# Guri_AVR.net
KiCad netlist of a schematic drawn in EAGLE
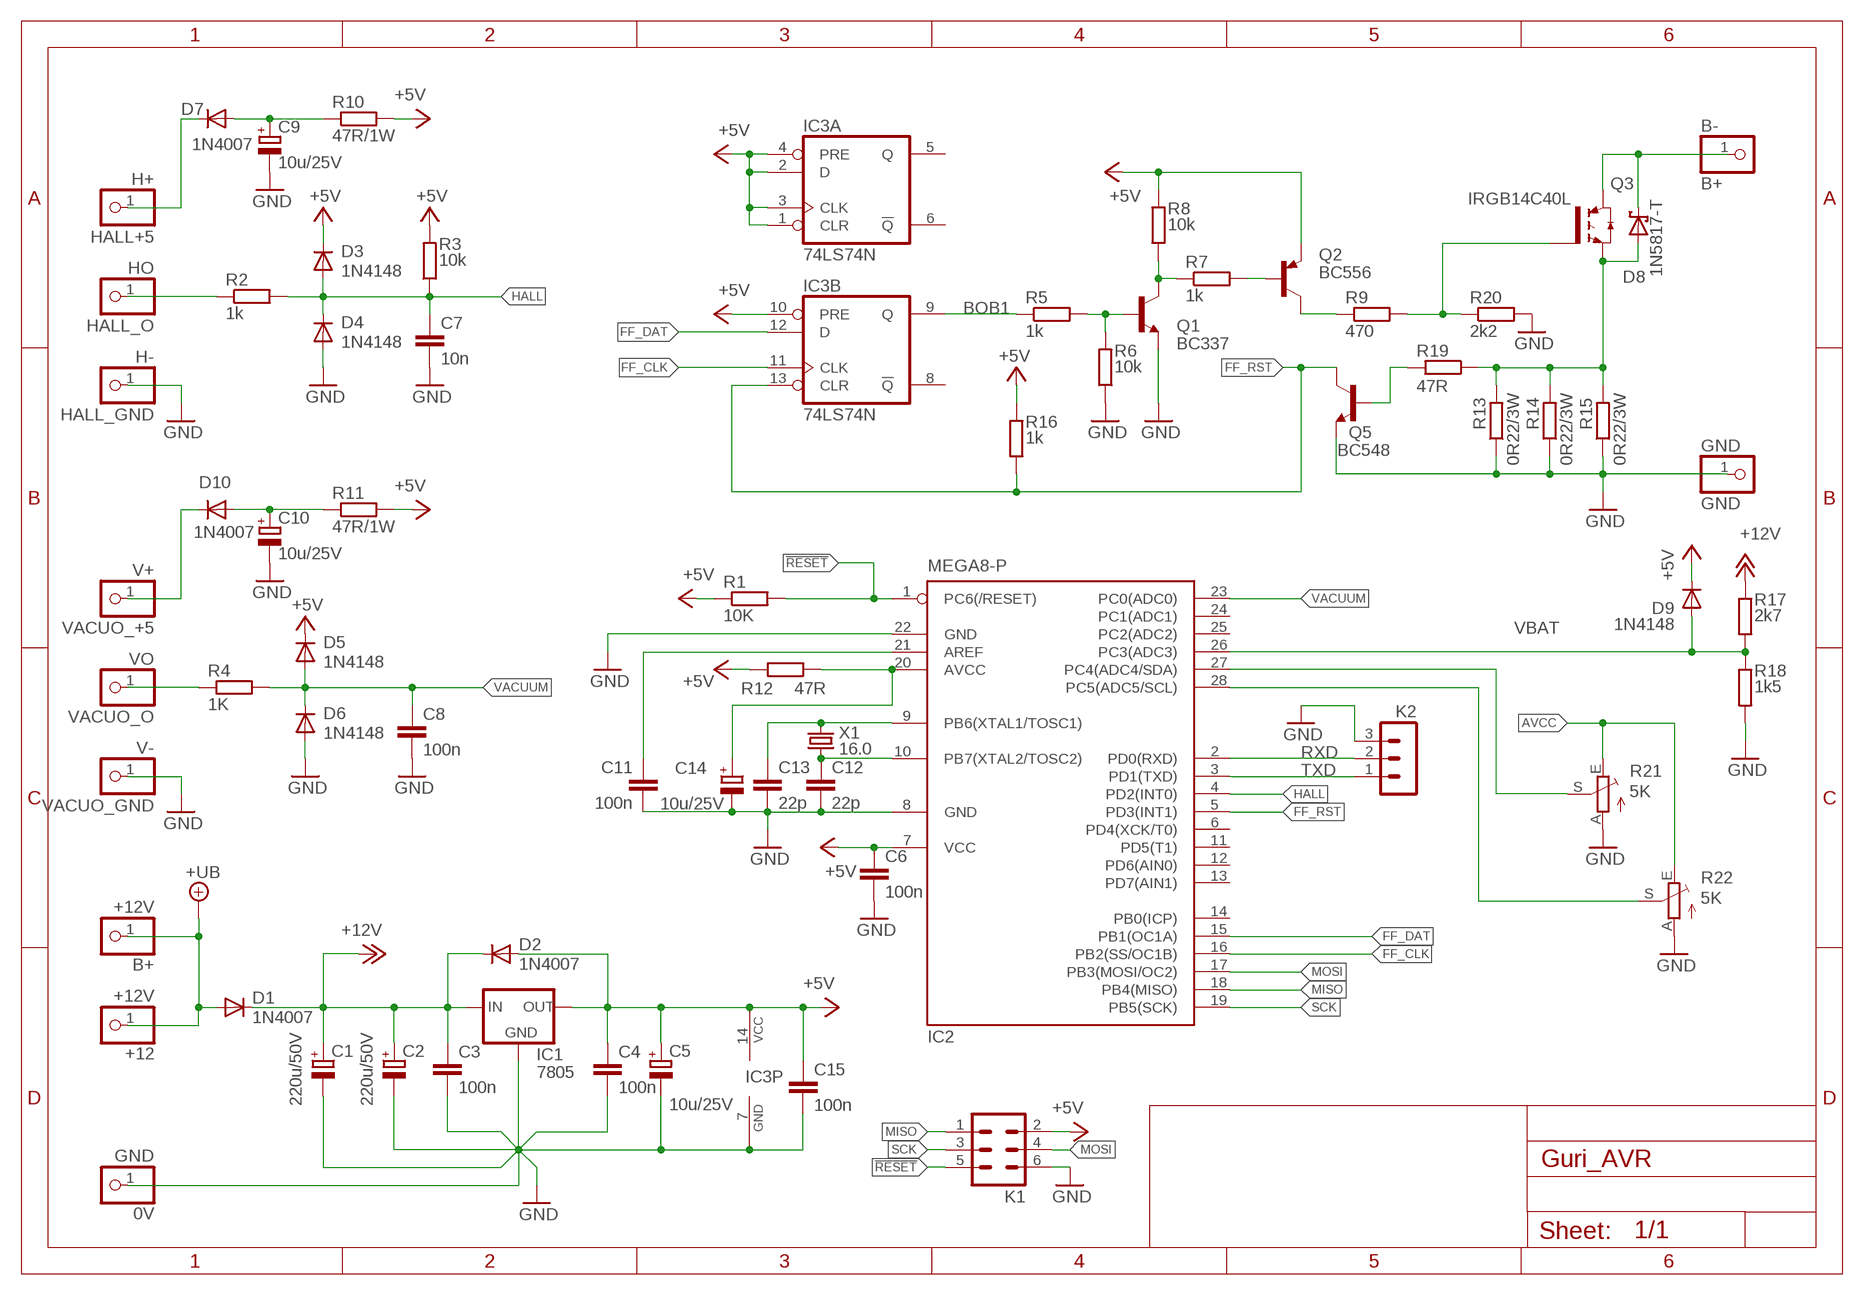
[diagram p0: schematic, sheet 1]

(export (version "E")
  (design (tool "Eeschema 10.0.6"))
  (components
    (comp (ref "+12")
      (value "+12V")
      (footprint "eagle-import:1X01")
      (libsource (lib "eagle-import") (part "PINHD-1X1"))
    )
    (comp (ref "0V")
      (value "GND")
      (footprint "eagle-import:1X01")
      (libsource (lib "eagle-import") (part "PINHD-1X1"))
    )
    (comp (ref "B+")
      (value "+12V")
      (footprint "eagle-import:1X01")
      (libsource (lib "eagle-import") (part "PINHD-1X1"))
    )
    (comp (ref "B-")
      (value "B+")
      (footprint "eagle-import:1X01")
      (libsource (lib "eagle-import") (part "PINHD-1X1"))
    )
    (comp (ref "C1")
      (value "220u/50V")
      (footprint "eagle-import:E5-10,5")
      (libsource (lib "eagle-import") (part "CPOL-EUE5-10.5"))
    )
    (comp (ref "C2")
      (value "220u/50V")
      (footprint "eagle-import:E5-10,5")
      (libsource (lib "eagle-import") (part "CPOL-EUE5-10.5"))
    )
    (comp (ref "C3")
      (value "100n")
      (footprint "eagle-import:C050-025X075")
      (libsource (lib "eagle-import") (part "C-EU050-025X075"))
    )
    (comp (ref "C4")
      (value "100n")
      (footprint "eagle-import:C050-025X075")
      (libsource (lib "eagle-import") (part "C-EU050-025X075"))
    )
    (comp (ref "C5")
      (value "10u/25V")
      (footprint "eagle-import:E2-5")
      (libsource (lib "eagle-import") (part "CPOL-EUE2-5"))
    )
    (comp (ref "C6")
      (value "100n")
      (footprint "eagle-import:C050-025X075")
      (libsource (lib "eagle-import") (part "C-EU050-025X075"))
    )
    (comp (ref "C7")
      (value "10n")
      (footprint "eagle-import:C050-025X075")
      (libsource (lib "eagle-import") (part "C-EU050-025X075"))
    )
    (comp (ref "C8")
      (value "100n")
      (footprint "eagle-import:C050-025X075")
      (libsource (lib "eagle-import") (part "C-EU050-025X075"))
    )
    (comp (ref "C9")
      (value "10u/25V")
      (footprint "eagle-import:E2-5")
      (libsource (lib "eagle-import") (part "CPOL-EUE2-5"))
    )
    (comp (ref "C10")
      (value "10u/25V")
      (footprint "eagle-import:E2-5")
      (libsource (lib "eagle-import") (part "CPOL-EUE2-5"))
    )
    (comp (ref "C11")
      (value "100n")
      (footprint "eagle-import:C050-025X075")
      (libsource (lib "eagle-import") (part "C-EU050-025X075"))
    )
    (comp (ref "C12")
      (value "22p")
      (footprint "eagle-import:C050-024X044")
      (libsource (lib "eagle-import") (part "C-EU050-024X044"))
    )
    (comp (ref "C13")
      (value "22p")
      (footprint "eagle-import:C050-024X044")
      (libsource (lib "eagle-import") (part "C-EU050-024X044"))
    )
    (comp (ref "C14")
      (value "10u/25V")
      (footprint "eagle-import:E2-5")
      (libsource (lib "eagle-import") (part "CPOL-EUE2-5"))
    )
    (comp (ref "C15")
      (value "100n")
      (footprint "eagle-import:C050-025X075")
      (libsource (lib "eagle-import") (part "C-EU050-025X075"))
    )
    (comp (ref "D1")
      (value "1N4007")
      (footprint "eagle-import:D-7.5")
      (libsource (lib "eagle-import") (part "DIODE-D-7.5"))
    )
    (comp (ref "D2")
      (value "1N4007")
      (footprint "eagle-import:D-7.5")
      (libsource (lib "eagle-import") (part "DIODE-D-7.5"))
    )
    (comp (ref "D3")
      (value "1N4148")
      (footprint "eagle-import:DO35-7")
      (libsource (lib "eagle-import") (part "1N4148DO35-7"))
    )
    (comp (ref "D4")
      (value "1N4148")
      (footprint "eagle-import:DO35-7")
      (libsource (lib "eagle-import") (part "1N4148DO35-7"))
    )
    (comp (ref "D5")
      (value "1N4148")
      (footprint "eagle-import:DO35-7")
      (libsource (lib "eagle-import") (part "1N4148DO35-7"))
    )
    (comp (ref "D6")
      (value "1N4148")
      (footprint "eagle-import:DO35-7")
      (libsource (lib "eagle-import") (part "1N4148DO35-7"))
    )
    (comp (ref "D7")
      (value "1N4007")
      (footprint "eagle-import:D-7.5")
      (libsource (lib "eagle-import") (part "DIODE-D-7.5"))
    )
    (comp (ref "D8")
      (value "1N5817-T")
      (footprint "eagle-import:DO41-7.6")
      (libsource (lib "eagle-import") (part "1N5817-T"))
    )
    (comp (ref "D9")
      (value "1N4148")
      (footprint "eagle-import:DO35-7")
      (libsource (lib "eagle-import") (part "1N4148DO35-7"))
    )
    (comp (ref "D10")
      (value "1N4007")
      (footprint "eagle-import:D-7.5")
      (libsource (lib "eagle-import") (part "DIODE-D-7.5"))
    )
    (comp (ref "GND")
      (value "GND")
      (footprint "eagle-import:1X01")
      (libsource (lib "eagle-import") (part "PINHD-1X1"))
    )
    (comp (ref "H+")
      (value "HALL+5")
      (footprint "eagle-import:1X01")
      (libsource (lib "eagle-import") (part "PINHD-1X1"))
    )
    (comp (ref "H-")
      (value "HALL_GND")
      (footprint "eagle-import:1X01")
      (libsource (lib "eagle-import") (part "PINHD-1X1"))
    )
    (comp (ref "HO")
      (value "HALL_O")
      (footprint "eagle-import:1X01")
      (libsource (lib "eagle-import") (part "PINHD-1X1"))
    )
    (comp (ref "IC1")
      (value "7805")
      (footprint "eagle-import:78XXS")
      (libsource (lib "eagle-import") (part "78XXS"))
    )
    (comp (ref "IC2")
      (value "MEGA8-P")
      (footprint "eagle-import:DIL28-3")
      (libsource (lib "eagle-import") (part "MEGA8-P"))
    )
    (comp (ref "IC3")
      (value "74LS74N")
      (footprint "eagle-import:DIL14")
      (libsource (lib "eagle-import") (part "7474NLS"))
    )
    (comp (ref "K1")
      (value "ML6")
      (footprint "eagle-import:ML6")
      (libsource (lib "eagle-import") (part "ML6"))
    )
    (comp (ref "K2")
      (value "MA03-1")
      (footprint "eagle-import:MA03-1")
      (libsource (lib "eagle-import") (part "MA03-1"))
    )
    (comp (ref "Q1")
      (value "BC337")
      (footprint "eagle-import:TO92-EBC")
      (libsource (lib "eagle-import") (part "BC338"))
    )
    (comp (ref "Q2")
      (value "BC556")
      (footprint "eagle-import:TO92-EBC")
      (libsource (lib "eagle-import") (part "BC556"))
    )
    (comp (ref "Q3")
      (value "IRGB14C40L")
      (footprint "eagle-import:TO262-V")
      (libsource (lib "eagle-import") (part "IRG4BC15UD--L"))
    )
    (comp (ref "Q5")
      (value "BC548")
      (footprint "eagle-import:TO92-EBC")
      (libsource (lib "eagle-import") (part "BC338"))
    )
    (comp (ref "R1")
      (value "10K")
      (footprint "eagle-import:0207_7L")
      (libsource (lib "eagle-import") (part "R-EU_0207/7L"))
    )
    (comp (ref "R2")
      (value "1k")
      (footprint "eagle-import:0207_7L")
      (libsource (lib "eagle-import") (part "R-EU_0207/7L"))
    )
    (comp (ref "R3")
      (value "10k")
      (footprint "eagle-import:0207_7L")
      (libsource (lib "eagle-import") (part "R-EU_0207/7L"))
    )
    (comp (ref "R4")
      (value "1K")
      (footprint "eagle-import:0207_7L")
      (libsource (lib "eagle-import") (part "R-EU_0207/7L"))
    )
    (comp (ref "R5")
      (value "1k")
      (footprint "eagle-import:0207_7L")
      (libsource (lib "eagle-import") (part "R-EU_0207/7L"))
    )
    (comp (ref "R6")
      (value "10k")
      (footprint "eagle-import:0207_7L")
      (libsource (lib "eagle-import") (part "R-EU_0207/7L"))
    )
    (comp (ref "R7")
      (value "1k")
      (footprint "eagle-import:0207_7L")
      (libsource (lib "eagle-import") (part "R-EU_0207/7L"))
    )
    (comp (ref "R8")
      (value "10k")
      (footprint "eagle-import:0207_7L")
      (libsource (lib "eagle-import") (part "R-EU_0207/7L"))
    )
    (comp (ref "R9")
      (value "470")
      (footprint "eagle-import:0207_7L")
      (libsource (lib "eagle-import") (part "R-EU_0207/7L"))
    )
    (comp (ref "R10")
      (value "47R/1W")
      (footprint "eagle-import:0207_7L")
      (libsource (lib "eagle-import") (part "R-EU_0207/7L"))
    )
    (comp (ref "R11")
      (value "47R/1W")
      (footprint "eagle-import:0207_7L")
      (libsource (lib "eagle-import") (part "R-EU_0207/7L"))
    )
    (comp (ref "R12")
      (value "47R")
      (footprint "eagle-import:0207_7L")
      (libsource (lib "eagle-import") (part "R-EU_0207/7L"))
    )
    (comp (ref "R13")
      (value "0R22/3W")
      (footprint "eagle-import:0309_10")
      (libsource (lib "eagle-import") (part "R-EU_0309/10"))
    )
    (comp (ref "R14")
      (value "0R22/3W")
      (footprint "eagle-import:0309_10")
      (libsource (lib "eagle-import") (part "R-EU_0309/10"))
    )
    (comp (ref "R15")
      (value "0R22/3W")
      (footprint "eagle-import:0309_10")
      (libsource (lib "eagle-import") (part "R-EU_0309/10"))
    )
    (comp (ref "R16")
      (value "1k")
      (footprint "eagle-import:0207_7L")
      (libsource (lib "eagle-import") (part "R-EU_0207/7L"))
    )
    (comp (ref "R17")
      (value "2k7")
      (footprint "eagle-import:0207_7L")
      (libsource (lib "eagle-import") (part "R-EU_0207/7L"))
    )
    (comp (ref "R18")
      (value "1k5")
      (footprint "eagle-import:0207_7L")
      (libsource (lib "eagle-import") (part "R-EU_0207/7L"))
    )
    (comp (ref "R19")
      (value "47R")
      (footprint "eagle-import:0207_7L")
      (libsource (lib "eagle-import") (part "R-EU_0207/7L"))
    )
    (comp (ref "R20")
      (value "2k2")
      (footprint "eagle-import:0207_7L")
      (libsource (lib "eagle-import") (part "R-EU_0207/7L"))
    )
    (comp (ref "R21")
      (value "5K")
      (footprint "eagle-import:ECP10P")
      (libsource (lib "eagle-import") (part "TRIM_EU-ECP10P"))
    )
    (comp (ref "R22")
      (value "5K")
      (footprint "eagle-import:ECP10P")
      (libsource (lib "eagle-import") (part "TRIM_EU-ECP10P"))
    )
    (comp (ref "V+")
      (value "VACUO_+5")
      (footprint "eagle-import:1X01")
      (libsource (lib "eagle-import") (part "PINHD-1X1"))
    )
    (comp (ref "V-")
      (value "VACUO_GND")
      (footprint "eagle-import:1X01")
      (libsource (lib "eagle-import") (part "PINHD-1X1"))
    )
    (comp (ref "VO")
      (value "VACUO_O")
      (footprint "eagle-import:1X01")
      (libsource (lib "eagle-import") (part "PINHD-1X1"))
    )
    (comp (ref "X1")
      (value "16.0")
      (footprint "eagle-import:HC49_S")
      (libsource (lib "eagle-import") (part "CRYSTALHC49S"))
    )
  )
  (nets
    (net (code "1") (name "+5V") (class "Default")
      (node (ref "C15") (pin "1") (pinfunction "1_1") (pintype "passive"))
      (node (ref "C4") (pin "1") (pinfunction "1_1") (pintype "passive"))
      (node (ref "C5") (pin "+") (pinfunction "+_+") (pintype "passive"))
      (node (ref "C6") (pin "1") (pinfunction "1_1") (pintype "passive"))
      (node (ref "D2") (pin "A") (pinfunction "A_A") (pintype "passive"))
      (node (ref "D3") (pin "C") (pinfunction "C_C") (pintype "passive"))
      (node (ref "D5") (pin "C") (pinfunction "C_C") (pintype "passive"))
      (node (ref "D9") (pin "C") (pinfunction "C_C") (pintype "passive"))
      (node (ref "IC1") (pin "OUT") (pinfunction "OUT_OUT") (pintype "passive"))
      (node (ref "IC2") (pin "7") (pinfunction "VCC_7") (pintype "power_in"))
      (node (ref "IC3") (pin "1") (pinfunction "CLR_1") (pintype "input"))
      (node (ref "IC3") (pin "10") (pinfunction "PRE_10") (pintype "input"))
      (node (ref "IC3") (pin "14") (pinfunction "VCC_14") (pintype "power_in"))
      (node (ref "IC3") (pin "2") (pinfunction "D_2") (pintype "input"))
      (node (ref "IC3") (pin "3") (pinfunction "CLK_3") (pintype "input"))
      (node (ref "IC3") (pin "4") (pinfunction "PRE_4") (pintype "input"))
      (node (ref "K1") (pin "2") (pinfunction "2_2") (pintype "passive"))
      (node (ref "Q2") (pin "E") (pinfunction "E_E") (pintype "passive"))
      (node (ref "R1") (pin "3") (pinfunction "1_3") (pintype "passive"))
      (node (ref "R10") (pin "4") (pinfunction "2_4") (pintype "passive"))
      (node (ref "R11") (pin "4") (pinfunction "2_4") (pintype "passive"))
      (node (ref "R12") (pin "4") (pinfunction "2_4") (pintype "passive"))
      (node (ref "R16") (pin "4") (pinfunction "2_4") (pintype "passive"))
      (node (ref "R3") (pin "4") (pinfunction "2_4") (pintype "passive"))
      (node (ref "R8") (pin "4") (pinfunction "2_4") (pintype "passive"))
    )
    (net (code "2") (name "+12V") (class "Default")
      (node (ref "C1") (pin "+") (pinfunction "+_+") (pintype "passive"))
      (node (ref "C2") (pin "+") (pinfunction "+_+") (pintype "passive"))
      (node (ref "C3") (pin "1") (pinfunction "1_1") (pintype "passive"))
      (node (ref "D1") (pin "C") (pinfunction "C_C") (pintype "passive"))
      (node (ref "D2") (pin "C") (pinfunction "C_C") (pintype "passive"))
      (node (ref "IC1") (pin "IN") (pinfunction "IN_IN") (pintype "input"))
      (node (ref "R17") (pin "3") (pinfunction "1_3") (pintype "passive"))
    )
    (net (code "3") (name "+UB") (class "Default")
      (node (ref "+12") (pin "1") (pinfunction "1_1") (pintype "passive"))
      (node (ref "B+") (pin "1") (pinfunction "1_1") (pintype "passive"))
      (node (ref "D1") (pin "A") (pinfunction "A_A") (pintype "passive"))
    )
    (net (code "4") (name "/BOB1") (class "Default")
      (node (ref "IC3") (pin "9") (pinfunction "Q_9") (pintype "output"))
      (node (ref "R5") (pin "3") (pinfunction "1_3") (pintype "passive"))
    )
    (net (code "5") (name "/RXD") (class "Default")
      (node (ref "IC2") (pin "2") (pinfunction "PD0(RXD)_2") (pintype "bidirectional"))
      (node (ref "K2") (pin "2") (pinfunction "2_2") (pintype "passive"))
    )
    (net (code "6") (name "/TXD") (class "Default")
      (node (ref "IC2") (pin "3") (pinfunction "PD1(TXD)_3") (pintype "bidirectional"))
      (node (ref "K2") (pin "1") (pinfunction "1_1") (pintype "passive"))
    )
    (net (code "7") (name "/VBAT") (class "Default")
      (node (ref "D9") (pin "A") (pinfunction "A_A") (pintype "passive"))
      (node (ref "IC2") (pin "26") (pinfunction "PC3(ADC3)_26") (pintype "bidirectional"))
      (node (ref "R17") (pin "4") (pinfunction "2_4") (pintype "passive"))
      (node (ref "R18") (pin "3") (pinfunction "1_3") (pintype "passive"))
    )
    (net (code "8") (name "/~{RESET}") (class "Default")
      (node (ref "IC2") (pin "1") (pinfunction "PC6(/RESET)_1") (pintype "bidirectional"))
      (node (ref "K1") (pin "5") (pinfunction "5_5") (pintype "passive"))
      (node (ref "R1") (pin "4") (pinfunction "2_4") (pintype "passive"))
    )
    (net (code "9") (name "AVCC") (class "Default")
      (node (ref "C14") (pin "+") (pinfunction "+_+") (pintype "passive"))
      (node (ref "IC2") (pin "20") (pinfunction "AVCC_20") (pintype "power_in"))
      (node (ref "R12") (pin "3") (pinfunction "1_3") (pintype "passive"))
      (node (ref "R21") (pin "E") (pinfunction "E_E") (pintype "passive"))
      (node (ref "R22") (pin "E") (pinfunction "E_E") (pintype "passive"))
    )
    (net (code "10") (name "FF_CLK") (class "Default")
      (node (ref "IC2") (pin "16") (pinfunction "PB2(SS/OC1B)_16") (pintype "bidirectional"))
      (node (ref "IC3") (pin "11") (pinfunction "CLK_11") (pintype "input"))
    )
    (net (code "11") (name "FF_DAT") (class "Default")
      (node (ref "IC2") (pin "15") (pinfunction "PB1(OC1A)_15") (pintype "bidirectional"))
      (node (ref "IC3") (pin "12") (pinfunction "D_12") (pintype "input"))
    )
    (net (code "12") (name "FF_RST") (class "Default")
      (node (ref "IC2") (pin "5") (pinfunction "PD3(INT1)_5") (pintype "bidirectional"))
      (node (ref "IC3") (pin "13") (pinfunction "CLR_13") (pintype "input"))
      (node (ref "Q5") (pin "C") (pinfunction "C_C") (pintype "passive"))
      (node (ref "R16") (pin "3") (pinfunction "1_3") (pintype "passive"))
    )
    (net (code "13") (name "GND") (class "Default")
      (node (ref "0V") (pin "1") (pinfunction "1_1") (pintype "passive"))
      (node (ref "C1") (pin "-") (pinfunction "-_-") (pintype "passive"))
      (node (ref "C10") (pin "-") (pinfunction "-_-") (pintype "passive"))
      (node (ref "C11") (pin "2") (pinfunction "2_2") (pintype "passive"))
      (node (ref "C12") (pin "2") (pinfunction "2_2") (pintype "passive"))
      (node (ref "C13") (pin "2") (pinfunction "2_2") (pintype "passive"))
      (node (ref "C14") (pin "-") (pinfunction "-_-") (pintype "passive"))
      (node (ref "C15") (pin "2") (pinfunction "2_2") (pintype "passive"))
      (node (ref "C2") (pin "-") (pinfunction "-_-") (pintype "passive"))
      (node (ref "C3") (pin "2") (pinfunction "2_2") (pintype "passive"))
      (node (ref "C4") (pin "2") (pinfunction "2_2") (pintype "passive"))
      (node (ref "C5") (pin "-") (pinfunction "-_-") (pintype "passive"))
      (node (ref "C6") (pin "2") (pinfunction "2_2") (pintype "passive"))
      (node (ref "C7") (pin "2") (pinfunction "2_2") (pintype "passive"))
      (node (ref "C8") (pin "2") (pinfunction "2_2") (pintype "passive"))
      (node (ref "C9") (pin "-") (pinfunction "-_-") (pintype "passive"))
      (node (ref "D4") (pin "A") (pinfunction "A_A") (pintype "passive"))
      (node (ref "D6") (pin "A") (pinfunction "A_A") (pintype "passive"))
      (node (ref "GND") (pin "1") (pinfunction "1_1") (pintype "passive"))
      (node (ref "H-") (pin "1") (pinfunction "1_1") (pintype "passive"))
      (node (ref "IC1") (pin "GND") (pinfunction "GND_GND") (pintype "input"))
      (node (ref "IC2") (pin "22") (pinfunction "GND_22") (pintype "power_in"))
      (node (ref "IC2") (pin "8") (pinfunction "GND_8") (pintype "power_in"))
      (node (ref "IC3") (pin "7") (pinfunction "GND_7") (pintype "power_in"))
      (node (ref "K1") (pin "6") (pinfunction "6_6") (pintype "passive"))
      (node (ref "K2") (pin "3") (pinfunction "3_3") (pintype "passive"))
      (node (ref "Q1") (pin "E") (pinfunction "E_E") (pintype "passive"))
      (node (ref "Q5") (pin "E") (pinfunction "E_E") (pintype "passive"))
      (node (ref "R13") (pin "1") (pinfunction "1_1") (pintype "passive"))
      (node (ref "R14") (pin "1") (pinfunction "1_1") (pintype "passive"))
      (node (ref "R15") (pin "1") (pinfunction "1_1") (pintype "passive"))
      (node (ref "R18") (pin "4") (pinfunction "2_4") (pintype "passive"))
      (node (ref "R20") (pin "4") (pinfunction "2_4") (pintype "passive"))
      (node (ref "R21") (pin "A") (pinfunction "A_A") (pintype "passive"))
      (node (ref "R22") (pin "A") (pinfunction "A_A") (pintype "passive"))
      (node (ref "R6") (pin "3") (pinfunction "1_3") (pintype "passive"))
      (node (ref "V-") (pin "1") (pinfunction "1_1") (pintype "passive"))
    )
    (net (code "14") (name "HALL") (class "Default")
      (node (ref "C7") (pin "1") (pinfunction "1_1") (pintype "passive"))
      (node (ref "D3") (pin "A") (pinfunction "A_A") (pintype "passive"))
      (node (ref "D4") (pin "C") (pinfunction "C_C") (pintype "passive"))
      (node (ref "IC2") (pin "4") (pinfunction "PD2(INT0)_4") (pintype "bidirectional"))
      (node (ref "R2") (pin "4") (pinfunction "2_4") (pintype "passive"))
      (node (ref "R3") (pin "3") (pinfunction "1_3") (pintype "passive"))
    )
    (net (code "15") (name "MISO") (class "Default")
      (node (ref "IC2") (pin "18") (pinfunction "PB4(MISO)_18") (pintype "bidirectional"))
      (node (ref "K1") (pin "1") (pinfunction "1_1") (pintype "passive"))
    )
    (net (code "16") (name "MOSI") (class "Default")
      (node (ref "IC2") (pin "17") (pinfunction "PB3(MOSI/OC2)_17") (pintype "bidirectional"))
      (node (ref "K1") (pin "4") (pinfunction "4_4") (pintype "passive"))
    )
    (net (code "17") (name "Net-(D7-PadC)") (class "Default")
      (node (ref "D7") (pin "C") (pinfunction "C_C") (pintype "passive"))
      (node (ref "H+") (pin "1") (pinfunction "1_1") (pintype "passive"))
    )
    (net (code "18") (name "Net-(D10-PadC)") (class "Default")
      (node (ref "D10") (pin "C") (pinfunction "C_C") (pintype "passive"))
      (node (ref "V+") (pin "1") (pinfunction "1_1") (pintype "passive"))
    )
    (net (code "19") (name "Net-(IC2-AREF)") (class "Default")
      (node (ref "C11") (pin "1") (pinfunction "1_1") (pintype "passive"))
      (node (ref "IC2") (pin "21") (pinfunction "AREF_21") (pintype "passive"))
    )
    (net (code "20") (name "Net-(IC2-PB6(XTAL1{slash}TOSC1))") (class "Default")
      (node (ref "C13") (pin "1") (pinfunction "1_1") (pintype "passive"))
      (node (ref "IC2") (pin "9") (pinfunction "PB6(XTAL1/TOSC1)_9") (pintype "bidirectional"))
      (node (ref "X1") (pin "2") (pinfunction "2_2") (pintype "passive"))
    )
    (net (code "21") (name "Net-(IC2-PB7(XTAL2{slash}TOSC2))") (class "Default")
      (node (ref "C12") (pin "1") (pinfunction "1_1") (pintype "passive"))
      (node (ref "IC2") (pin "10") (pinfunction "PB7(XTAL2/TOSC2)_10") (pintype "bidirectional"))
      (node (ref "X1") (pin "1") (pinfunction "1_1") (pintype "passive"))
    )
    (net (code "22") (name "Net-(IC2-PC4(ADC4{slash}SDA))") (class "Default")
      (node (ref "IC2") (pin "27") (pinfunction "PC4(ADC4/SDA)_27") (pintype "bidirectional"))
      (node (ref "R21") (pin "S") (pinfunction "S_S") (pintype "passive"))
    )
    (net (code "23") (name "Net-(IC2-PC5(ADC5{slash}SCL))") (class "Default")
      (node (ref "IC2") (pin "28") (pinfunction "PC5(ADC5/SCL)_28") (pintype "bidirectional"))
      (node (ref "R22") (pin "S") (pinfunction "S_S") (pintype "passive"))
    )
    (net (code "24") (name "Net-(Q3-C)") (class "Default")
      (node (ref "B-") (pin "1") (pinfunction "1_1") (pintype "passive"))
      (node (ref "D8") (pin "C") (pinfunction "C_C") (pintype "passive"))
      (node (ref "Q3") (pin "2") (pinfunction "C_2") (pintype "passive"))
    )
    (net (code "25") (name "Net-(Q3-E)") (class "Default")
      (node (ref "D8") (pin "A") (pinfunction "A_A") (pintype "passive"))
      (node (ref "Q3") (pin "3") (pinfunction "E_3") (pintype "passive"))
      (node (ref "R13") (pin "2") (pinfunction "2_2") (pintype "passive"))
      (node (ref "R14") (pin "2") (pinfunction "2_2") (pintype "passive"))
      (node (ref "R15") (pin "2") (pinfunction "2_2") (pintype "passive"))
      (node (ref "R19") (pin "3") (pinfunction "1_3") (pintype "passive"))
    )
    (net (code "26") (name "Net-(Q3-G)") (class "Default")
      (node (ref "Q3") (pin "1") (pinfunction "G_1") (pintype "passive"))
      (node (ref "R20") (pin "3") (pinfunction "1_3") (pintype "passive"))
      (node (ref "R9") (pin "4") (pinfunction "2_4") (pintype "passive"))
    )
    (net (code "27") (name "Net-(R2-1)") (class "Default")
      (node (ref "HO") (pin "1") (pinfunction "1_1") (pintype "passive"))
      (node (ref "R2") (pin "3") (pinfunction "1_3") (pintype "passive"))
    )
    (net (code "28") (name "Net-(R4-1)") (class "Default")
      (node (ref "R4") (pin "3") (pinfunction "1_3") (pintype "passive"))
      (node (ref "VO") (pin "1") (pinfunction "1_1") (pintype "passive"))
    )
    (net (code "29") (name "Net-(R5-2)") (class "Default")
      (node (ref "Q1") (pin "B") (pinfunction "B_B") (pintype "passive"))
      (node (ref "R5") (pin "4") (pinfunction "2_4") (pintype "passive"))
      (node (ref "R6") (pin "4") (pinfunction "2_4") (pintype "passive"))
    )
    (net (code "30") (name "Net-(R7-1)") (class "Default")
      (node (ref "Q1") (pin "C") (pinfunction "C_C") (pintype "passive"))
      (node (ref "R7") (pin "3") (pinfunction "1_3") (pintype "passive"))
      (node (ref "R8") (pin "3") (pinfunction "1_3") (pintype "passive"))
    )
    (net (code "31") (name "Net-(R7-2)") (class "Default")
      (node (ref "Q2") (pin "B") (pinfunction "B_B") (pintype "passive"))
      (node (ref "R7") (pin "4") (pinfunction "2_4") (pintype "passive"))
    )
    (net (code "32") (name "Net-(R9-1)") (class "Default")
      (node (ref "Q2") (pin "C") (pinfunction "C_C") (pintype "passive"))
      (node (ref "R9") (pin "3") (pinfunction "1_3") (pintype "passive"))
    )
    (net (code "33") (name "Net-(R10-1)") (class "Default")
      (node (ref "C9") (pin "+") (pinfunction "+_+") (pintype "passive"))
      (node (ref "D7") (pin "A") (pinfunction "A_A") (pintype "passive"))
      (node (ref "R10") (pin "3") (pinfunction "1_3") (pintype "passive"))
    )
    (net (code "34") (name "Net-(R11-1)") (class "Default")
      (node (ref "C10") (pin "+") (pinfunction "+_+") (pintype "passive"))
      (node (ref "D10") (pin "A") (pinfunction "A_A") (pintype "passive"))
      (node (ref "R11") (pin "3") (pinfunction "1_3") (pintype "passive"))
    )
    (net (code "35") (name "Net-(R19-2)") (class "Default")
      (node (ref "Q5") (pin "B") (pinfunction "B_B") (pintype "passive"))
      (node (ref "R19") (pin "4") (pinfunction "2_4") (pintype "passive"))
    )
    (net (code "36") (name "SCK") (class "Default")
      (node (ref "IC2") (pin "19") (pinfunction "PB5(SCK)_19") (pintype "bidirectional"))
      (node (ref "K1") (pin "3") (pinfunction "3_3") (pintype "passive"))
    )
    (net (code "37") (name "VACUUM") (class "Default")
      (node (ref "C8") (pin "1") (pinfunction "1_1") (pintype "passive"))
      (node (ref "D5") (pin "A") (pinfunction "A_A") (pintype "passive"))
      (node (ref "D6") (pin "C") (pinfunction "C_C") (pintype "passive"))
      (node (ref "IC2") (pin "23") (pinfunction "PC0(ADC0)_23") (pintype "bidirectional"))
      (node (ref "R4") (pin "4") (pinfunction "2_4") (pintype "passive"))
    )
    (net (code "38") (name "unconnected-(IC2-PB0(ICP)-Pad14)") (class "Default")
      (node (ref "IC2") (pin "14") (pinfunction "PB0(ICP)_14") (pintype "bidirectional"))
    )
    (net (code "39") (name "unconnected-(IC2-PC1(ADC1)-Pad24)") (class "Default")
      (node (ref "IC2") (pin "24") (pinfunction "PC1(ADC1)_24") (pintype "bidirectional"))
    )
    (net (code "40") (name "unconnected-(IC2-PC2(ADC2)-Pad25)") (class "Default")
      (node (ref "IC2") (pin "25") (pinfunction "PC2(ADC2)_25") (pintype "bidirectional"))
    )
    (net (code "41") (name "unconnected-(IC2-PD4(XCK{slash}T0)-Pad6)") (class "Default")
      (node (ref "IC2") (pin "6") (pinfunction "PD4(XCK/T0)_6") (pintype "bidirectional"))
    )
    (net (code "42") (name "unconnected-(IC2-PD5(T1)-Pad11)") (class "Default")
      (node (ref "IC2") (pin "11") (pinfunction "PD5(T1)_11") (pintype "bidirectional"))
    )
    (net (code "43") (name "unconnected-(IC2-PD6(AIN0)-Pad12)") (class "Default")
      (node (ref "IC2") (pin "12") (pinfunction "PD6(AIN0)_12") (pintype "bidirectional"))
    )
    (net (code "44") (name "unconnected-(IC2-PD7(AIN1)-Pad13)") (class "Default")
      (node (ref "IC2") (pin "13") (pinfunction "PD7(AIN1)_13") (pintype "bidirectional"))
    )
    (net (code "45") (name "unconnected-(IC3A-Q-Pad5)") (class "Default")
      (node (ref "IC3") (pin "5") (pinfunction "Q_5") (pintype "output"))
    )
    (net (code "46") (name "unconnected-(IC3A-~{Q}-Pad6)") (class "Default")
      (node (ref "IC3") (pin "6") (pinfunction "~{Q}_6") (pintype "output"))
    )
    (net (code "47") (name "unconnected-(IC3B-~{Q}-Pad8)") (class "Default")
      (node (ref "IC3") (pin "8") (pinfunction "~{Q}_8") (pintype "output"))
    )
  )
)
